# mechanics.net
KiCad netlist of a schematic drawn in Altium Designer
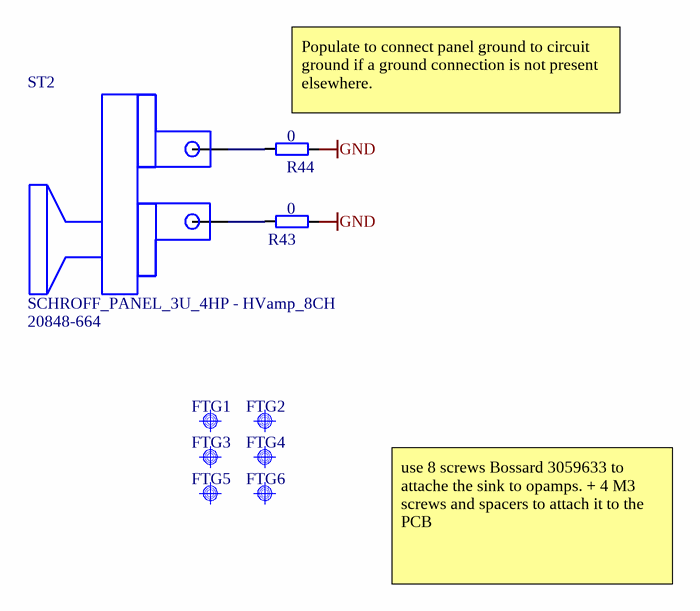
[diagram p0: mechanics.SchDoc]

(export (version "E")
  (design (tool "Eeschema 10.0.6"))
  (components
    (comp (ref "FTG1")
      (value "Use only in PCB")
      (footprint "FIDUCIAL_TOP_C100-200")
      (description "Fiducial Target")
      (fields (field (name "PART NUMBER") "FIDUCIAL_TARGET_C100-200") (field (name "AUTHOR") "CERN DEM JLC"))
      (libsource (lib "Eletro-mechanical") (part "Fiducial Target"))
    )
    (comp (ref "FTG2")
      (value "Use only in PCB")
      (footprint "FIDUCIAL_TOP_C100-200")
      (description "Fiducial Target")
      (fields (field (name "PART NUMBER") "FIDUCIAL_TARGET_C100-200") (field (name "AUTHOR") "CERN DEM JLC"))
      (libsource (lib "Eletro-mechanical") (part "Fiducial Target"))
    )
    (comp (ref "FTG3")
      (value "Use only in PCB")
      (footprint "FIDUCIAL_TOP_C100-200")
      (description "Fiducial Target")
      (fields (field (name "PART NUMBER") "FIDUCIAL_TARGET_C100-200") (field (name "AUTHOR") "CERN DEM JLC"))
      (libsource (lib "Eletro-mechanical") (part "Fiducial Target"))
    )
    (comp (ref "FTG4")
      (value "Use only in PCB")
      (footprint "FIDUCIAL_TOP_C100-200")
      (description "Fiducial Target")
      (fields (field (name "PART NUMBER") "FIDUCIAL_TARGET_C100-200") (field (name "AUTHOR") "CERN DEM JLC"))
      (libsource (lib "Eletro-mechanical") (part "Fiducial Target"))
    )
    (comp (ref "FTG5")
      (value "Use only in PCB")
      (footprint "FIDUCIAL_TOP_C100-200")
      (description "Fiducial Target")
      (fields (field (name "PART NUMBER") "FIDUCIAL_TARGET_C100-200") (field (name "AUTHOR") "CERN DEM JLC"))
      (libsource (lib "Eletro-mechanical") (part "Fiducial Target"))
    )
    (comp (ref "FTG6")
      (value "Use only in PCB")
      (footprint "FIDUCIAL_TOP_C100-200")
      (description "Fiducial Target")
      (fields (field (name "PART NUMBER") "FIDUCIAL_TARGET_C100-200") (field (name "AUTHOR") "CERN DEM JLC"))
      (libsource (lib "Eletro-mechanical") (part "Fiducial Target"))
    )
    (comp (ref "R43")
      (value "0")
      (footprint "RESC1608X55N")
      (description "Resistor")
      (fields
        (field (name "PART NUMBER") "R0603_0R_JUMPER")
        (field (name "MANUFACTURER") "GENERIC")
        (field (name "AUTHOR") "CERN DEM JLC")
      )
      (libsource (lib "Resistors") (part "Resistor"))
    )
    (comp (ref "R44")
      (value "0")
      (footprint "RESC1608X55N")
      (description "Resistor")
      (fields
        (field (name "PART NUMBER") "R0603_0R_JUMPER")
        (field (name "MANUFACTURER") "GENERIC")
        (field (name "AUTHOR") "CERN DEM JLC")
      )
      (libsource (lib "Resistors") (part "Resistor"))
    )
    (comp (ref "ST2")
      (value "SCHROFF_PANEL_3U_4HP - HVamp_8CH")
      (footprint "SCHROFF_PANEL_3U_4HP - HVamp_8CH")
      (description "Schroff 3HP 4U EUROCARD Panel")
      (fields
        (field (name "MANUFACTURER") "Schroff")
        (field (name "MANUFACTURER PART NUMBER") "20818-017")
        (field (name "MANUFACTURER PART NUMBER 2") "20848-664")
      )
      (libsource (lib "Mechanical") (part "SCHROFF_PANEL_3U_4HP - HVamp_8CH"))
    )
  )
  (nets
    (net (code "1") (name "GND") (class "Default")
      (node (ref "R43") (pin "1") (pinfunction "1_1") (pintype "passive"))
      (node (ref "R44") (pin "1") (pinfunction "1_1") (pintype "passive"))
    )
    (net (code "2") (name "Net-(R43-Pad2)") (class "Default")
      (node (ref "R43") (pin "2") (pinfunction "2_2") (pintype "passive"))
      (node (ref "ST2") (pin "0") (pinfunction "0_0") (pintype "passive"))
    )
    (net (code "3") (name "Net-(R44-Pad2)") (class "Default")
      (node (ref "R44") (pin "2") (pinfunction "2_2") (pintype "passive"))
      (node (ref "ST2") (pin "1") (pinfunction "1_1") (pintype "passive"))
    )
  )
)
